# Nikola98p_M_2-ESP32-S3_N16R8-Dev-Board__.net
KiCad netlist of a schematic drawn in Altium Designer
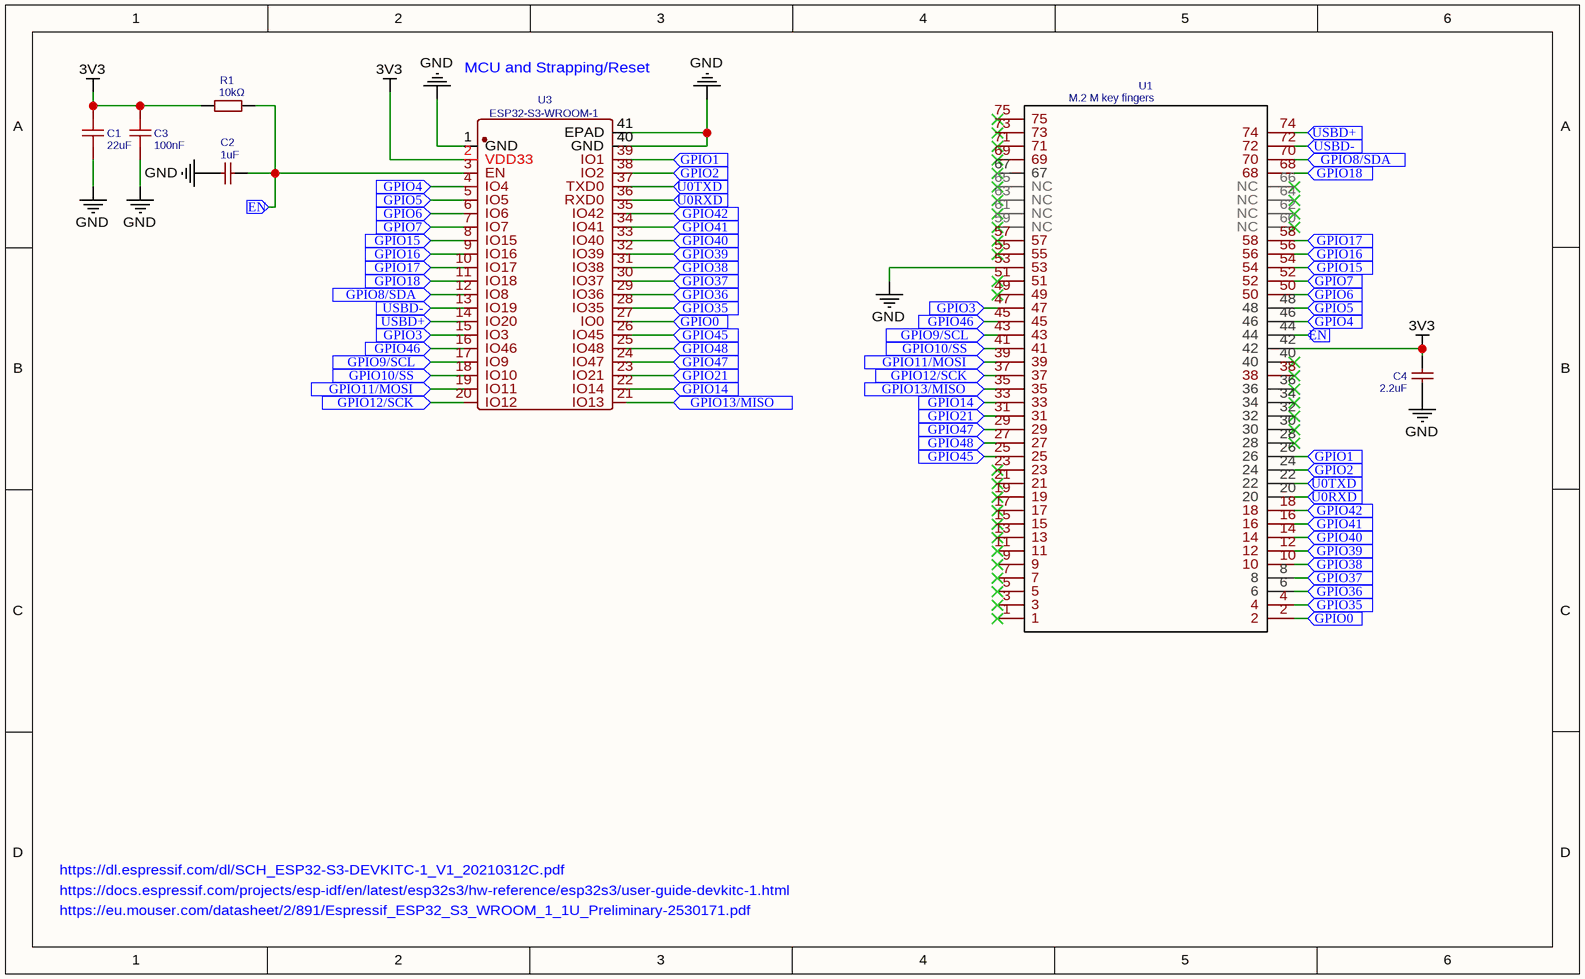
[diagram p0: Nikola98p_M.2-ESP32-S3_N16R8-Dev-Board__Altium__ESP32-S3-M.2_2024-03-15.schdoc]

(export (version "E")
  (design (tool "Eeschema 10.0.6"))
  (components
    (comp (ref "C1")
      (value "22uF")
      (fields
        (field (name "MANUFACTURER") "SAMSUNG(三星)")
        (field (name "MANUFACTURER PART") "CL10A226MQ8NRNC")
      )
      (libsource (lib "altium-import") (part "root_1_22uF_"))
    )
    (comp (ref "C2")
      (value "1uF")
      (fields
        (field (name "MANUFACTURER PART") "CL10A105KB8NNNC")
        (field (name "MANUFACTURER") "SAMSUNG(三星)")
      )
      (libsource (lib "altium-import") (part "root_0_1uF_"))
    )
    (comp (ref "C3")
      (value "100nF")
      (fields
        (field (name "MANUFACTURER") "YAGEO(国巨)")
        (field (name "MANUFACTURER PART") "CC0603KRX7R9BB104")
      )
      (libsource (lib "altium-import") (part "root_1_100nF_"))
    )
    (comp (ref "C4")
      (value "2.2uF")
      (fields
        (field (name "MANUFACTURER PART") "CL10A225KP8NNNC")
        (field (name "MANUFACTURER") "SAMSUNG(三星)")
      )
      (libsource (lib "altium-import") (part "root_1_2.2uF_"))
    )
    (comp (ref "R1")
      (value "10kΩ")
      (fields (field (name "MANUFACTURER") "YAGEO(国巨)") (field (name "MANUFACTURER PART") "RC0603FR-0710KL"))
      (libsource (lib "altium-import") (part "root_0_10kΩ_"))
    )
    (comp (ref "U1")
      (value "M.2 M key fingers")
      (fields (field (name "CONTRIBUTOR") "Nikola Pantelin"))
      (libsource (lib "altium-import") (part "root_0_M.2 M key fingers_"))
    )
    (comp (ref "U3")
      (value "ESP32-S3-WROOM-1")
      (fields (field (name "MANUFACTURER") "Espressif Systems") (field (name "CONTRIBUTOR") "max30012540"))
      (libsource (lib "altium-import") (part "root_0_ESP32-S3-WROOM-1_"))
    )
  )
  (nets
    (net (code "1") (name "/EN") (class "Default")
      (node (ref "C2") (pin "2") (pinfunction "2_2") (pintype "passive"))
      (node (ref "R1") (pin "2") (pinfunction "2_2") (pintype "passive"))
      (node (ref "U1") (pin "44") (pinfunction "44_44") (pintype "passive"))
      (node (ref "U3") (pin "3") (pinfunction "EN_3") (pintype "passive"))
    )
    (net (code "2") (name "/GPIO0") (class "Default")
      (node (ref "U1") (pin "2") (pinfunction "2_2") (pintype "passive"))
      (node (ref "U3") (pin "27") (pinfunction "IO0_27") (pintype "passive"))
    )
    (net (code "3") (name "/GPIO1") (class "Default")
      (node (ref "U1") (pin "26") (pinfunction "26_26") (pintype "passive"))
      (node (ref "U3") (pin "39") (pinfunction "IO1_39") (pintype "passive"))
    )
    (net (code "4") (name "/GPIO2") (class "Default")
      (node (ref "U1") (pin "24") (pinfunction "24_24") (pintype "passive"))
      (node (ref "U3") (pin "38") (pinfunction "IO2_38") (pintype "passive"))
    )
    (net (code "5") (name "/GPIO3") (class "Default")
      (node (ref "U1") (pin "47") (pinfunction "47_47") (pintype "passive"))
      (node (ref "U3") (pin "15") (pinfunction "IO3_15") (pintype "passive"))
    )
    (net (code "6") (name "/GPIO4") (class "Default")
      (node (ref "U1") (pin "46") (pinfunction "46_46") (pintype "passive"))
      (node (ref "U3") (pin "4") (pinfunction "IO4_4") (pintype "passive"))
    )
    (net (code "7") (name "/GPIO5") (class "Default")
      (node (ref "U1") (pin "48") (pinfunction "48_48") (pintype "passive"))
      (node (ref "U3") (pin "5") (pinfunction "IO5_5") (pintype "passive"))
    )
    (net (code "8") (name "/GPIO6") (class "Default")
      (node (ref "U1") (pin "50") (pinfunction "50_50") (pintype "passive"))
      (node (ref "U3") (pin "6") (pinfunction "IO6_6") (pintype "passive"))
    )
    (net (code "9") (name "/GPIO7") (class "Default")
      (node (ref "U1") (pin "52") (pinfunction "52_52") (pintype "passive"))
      (node (ref "U3") (pin "7") (pinfunction "IO7_7") (pintype "passive"))
    )
    (net (code "10") (name "/GPIO8{slash}SDA") (class "Default")
      (node (ref "U1") (pin "70") (pinfunction "70_70") (pintype "passive"))
      (node (ref "U3") (pin "12") (pinfunction "IO8_12") (pintype "passive"))
    )
    (net (code "11") (name "/GPIO9{slash}SCL") (class "Default")
      (node (ref "U1") (pin "43") (pinfunction "43_43") (pintype "passive"))
      (node (ref "U3") (pin "17") (pinfunction "IO9_17") (pintype "passive"))
    )
    (net (code "12") (name "/GPIO10{slash}SS") (class "Default")
      (node (ref "U1") (pin "41") (pinfunction "41_41") (pintype "passive"))
      (node (ref "U3") (pin "18") (pinfunction "IO10_18") (pintype "passive"))
    )
    (net (code "13") (name "/GPIO11{slash}MOSI") (class "Default")
      (node (ref "U1") (pin "39") (pinfunction "39_39") (pintype "passive"))
      (node (ref "U3") (pin "19") (pinfunction "IO11_19") (pintype "passive"))
    )
    (net (code "14") (name "/GPIO12{slash}SCK") (class "Default")
      (node (ref "U1") (pin "37") (pinfunction "37_37") (pintype "passive"))
      (node (ref "U3") (pin "20") (pinfunction "IO12_20") (pintype "passive"))
    )
    (net (code "15") (name "/GPIO13{slash}MISO") (class "Default")
      (node (ref "U1") (pin "35") (pinfunction "35_35") (pintype "passive"))
      (node (ref "U3") (pin "21") (pinfunction "IO13_21") (pintype "passive"))
    )
    (net (code "16") (name "/GPIO14") (class "Default")
      (node (ref "U1") (pin "33") (pinfunction "33_33") (pintype "passive"))
      (node (ref "U3") (pin "22") (pinfunction "IO14_22") (pintype "passive"))
    )
    (net (code "17") (name "/GPIO15") (class "Default")
      (node (ref "U1") (pin "54") (pinfunction "54_54") (pintype "passive"))
      (node (ref "U3") (pin "8") (pinfunction "IO15_8") (pintype "passive"))
    )
    (net (code "18") (name "/GPIO16") (class "Default")
      (node (ref "U1") (pin "56") (pinfunction "56_56") (pintype "passive"))
      (node (ref "U3") (pin "9") (pinfunction "IO16_9") (pintype "passive"))
    )
    (net (code "19") (name "/GPIO17") (class "Default")
      (node (ref "U1") (pin "58") (pinfunction "58_58") (pintype "passive"))
      (node (ref "U3") (pin "10") (pinfunction "IO17_10") (pintype "passive"))
    )
    (net (code "20") (name "/GPIO18") (class "Default")
      (node (ref "U1") (pin "68") (pinfunction "68_68") (pintype "passive"))
      (node (ref "U3") (pin "11") (pinfunction "IO18_11") (pintype "passive"))
    )
    (net (code "21") (name "/GPIO21") (class "Default")
      (node (ref "U1") (pin "31") (pinfunction "31_31") (pintype "passive"))
      (node (ref "U3") (pin "23") (pinfunction "IO21_23") (pintype "passive"))
    )
    (net (code "22") (name "/GPIO35") (class "Default")
      (node (ref "U1") (pin "4") (pinfunction "4_4") (pintype "passive"))
      (node (ref "U3") (pin "28") (pinfunction "IO35_28") (pintype "passive"))
    )
    (net (code "23") (name "/GPIO36") (class "Default")
      (node (ref "U1") (pin "6") (pinfunction "6_6") (pintype "passive"))
      (node (ref "U3") (pin "29") (pinfunction "IO36_29") (pintype "passive"))
    )
    (net (code "24") (name "/GPIO37") (class "Default")
      (node (ref "U1") (pin "8") (pinfunction "8_8") (pintype "passive"))
      (node (ref "U3") (pin "30") (pinfunction "IO37_30") (pintype "passive"))
    )
    (net (code "25") (name "/GPIO38") (class "Default")
      (node (ref "U1") (pin "10") (pinfunction "10_10") (pintype "passive"))
      (node (ref "U3") (pin "31") (pinfunction "IO38_31") (pintype "passive"))
    )
    (net (code "26") (name "/GPIO39") (class "Default")
      (node (ref "U1") (pin "12") (pinfunction "12_12") (pintype "passive"))
      (node (ref "U3") (pin "32") (pinfunction "IO39_32") (pintype "passive"))
    )
    (net (code "27") (name "/GPIO40") (class "Default")
      (node (ref "U1") (pin "14") (pinfunction "14_14") (pintype "passive"))
      (node (ref "U3") (pin "33") (pinfunction "IO40_33") (pintype "passive"))
    )
    (net (code "28") (name "/GPIO41") (class "Default")
      (node (ref "U1") (pin "16") (pinfunction "16_16") (pintype "passive"))
      (node (ref "U3") (pin "34") (pinfunction "IO41_34") (pintype "passive"))
    )
    (net (code "29") (name "/GPIO42") (class "Default")
      (node (ref "U1") (pin "18") (pinfunction "18_18") (pintype "passive"))
      (node (ref "U3") (pin "35") (pinfunction "IO42_35") (pintype "passive"))
    )
    (net (code "30") (name "/GPIO45") (class "Default")
      (node (ref "U1") (pin "25") (pinfunction "25_25") (pintype "passive"))
      (node (ref "U3") (pin "26") (pinfunction "IO45_26") (pintype "passive"))
    )
    (net (code "31") (name "/GPIO46") (class "Default")
      (node (ref "U1") (pin "45") (pinfunction "45_45") (pintype "passive"))
      (node (ref "U3") (pin "16") (pinfunction "IO46_16") (pintype "passive"))
    )
    (net (code "32") (name "/GPIO47") (class "Default")
      (node (ref "U1") (pin "29") (pinfunction "29_29") (pintype "passive"))
      (node (ref "U3") (pin "24") (pinfunction "IO47_24") (pintype "passive"))
    )
    (net (code "33") (name "/GPIO48") (class "Default")
      (node (ref "U1") (pin "27") (pinfunction "27_27") (pintype "passive"))
      (node (ref "U3") (pin "25") (pinfunction "IO48_25") (pintype "passive"))
    )
    (net (code "34") (name "/U0RXD") (class "Default")
      (node (ref "U1") (pin "20") (pinfunction "20_20") (pintype "passive"))
      (node (ref "U3") (pin "36") (pinfunction "RXD0_36") (pintype "passive"))
    )
    (net (code "35") (name "/U0TXD") (class "Default")
      (node (ref "U1") (pin "22") (pinfunction "22_22") (pintype "passive"))
      (node (ref "U3") (pin "37") (pinfunction "TXD0_37") (pintype "passive"))
    )
    (net (code "36") (name "/USBD+") (class "Default")
      (node (ref "U1") (pin "74") (pinfunction "74_74") (pintype "passive"))
      (node (ref "U3") (pin "14") (pinfunction "IO20_14") (pintype "passive"))
    )
    (net (code "37") (name "/USBD-") (class "Default")
      (node (ref "U1") (pin "72") (pinfunction "72_72") (pintype "passive"))
      (node (ref "U3") (pin "13") (pinfunction "IO19_13") (pintype "passive"))
    )
    (net (code "38") (name "3V3") (class "Default")
      (node (ref "C1") (pin "2") (pinfunction "2_2") (pintype "passive"))
      (node (ref "C3") (pin "2") (pinfunction "2_2") (pintype "passive"))
      (node (ref "C4") (pin "2") (pinfunction "2_2") (pintype "passive"))
      (node (ref "R1") (pin "1") (pinfunction "1_1") (pintype "passive"))
      (node (ref "U1") (pin "42") (pinfunction "42_42") (pintype "passive"))
      (node (ref "U3") (pin "2") (pinfunction "VDD33_2") (pintype "passive"))
    )
    (net (code "39") (name "GND") (class "Default")
      (node (ref "C1") (pin "1") (pinfunction "1_1") (pintype "passive"))
      (node (ref "C2") (pin "1") (pinfunction "1_1") (pintype "passive"))
      (node (ref "C3") (pin "1") (pinfunction "1_1") (pintype "passive"))
      (node (ref "C4") (pin "1") (pinfunction "1_1") (pintype "passive"))
      (node (ref "U1") (pin "53") (pinfunction "53_53") (pintype "passive"))
      (node (ref "U3") (pin "1") (pinfunction "GND_1") (pintype "passive"))
      (node (ref "U3") (pin "40") (pinfunction "GND_40") (pintype "passive"))
      (node (ref "U3") (pin "41") (pinfunction "EPAD_41") (pintype "passive"))
    )
    (net (code "40") (name "unconnected-(U1-NC-Pad59)") (class "Default")
      (node (ref "U1") (pin "59") (pinfunction "NC_59") (pintype "passive+no_connect"))
    )
    (net (code "41") (name "unconnected-(U1-NC-Pad60)") (class "Default")
      (node (ref "U1") (pin "60") (pinfunction "NC_60") (pintype "passive+no_connect"))
    )
    (net (code "42") (name "unconnected-(U1-NC-Pad61)") (class "Default")
      (node (ref "U1") (pin "61") (pinfunction "NC_61") (pintype "passive+no_connect"))
    )
    (net (code "43") (name "unconnected-(U1-NC-Pad62)") (class "Default")
      (node (ref "U1") (pin "62") (pinfunction "NC_62") (pintype "passive+no_connect"))
    )
    (net (code "44") (name "unconnected-(U1-NC-Pad63)") (class "Default")
      (node (ref "U1") (pin "63") (pinfunction "NC_63") (pintype "passive+no_connect"))
    )
    (net (code "45") (name "unconnected-(U1-NC-Pad64)") (class "Default")
      (node (ref "U1") (pin "64") (pinfunction "NC_64") (pintype "passive+no_connect"))
    )
    (net (code "46") (name "unconnected-(U1-NC-Pad65)") (class "Default")
      (node (ref "U1") (pin "65") (pinfunction "NC_65") (pintype "passive+no_connect"))
    )
    (net (code "47") (name "unconnected-(U1-NC-Pad66)") (class "Default")
      (node (ref "U1") (pin "66") (pinfunction "NC_66") (pintype "passive+no_connect"))
    )
    (net (code "48") (name "unconnected-(U1-Pad1)") (class "Default")
      (node (ref "U1") (pin "1") (pinfunction "1_1") (pintype "passive+no_connect"))
    )
    (net (code "49") (name "unconnected-(U1-Pad3)") (class "Default")
      (node (ref "U1") (pin "3") (pinfunction "3_3") (pintype "passive+no_connect"))
    )
    (net (code "50") (name "unconnected-(U1-Pad5)") (class "Default")
      (node (ref "U1") (pin "5") (pinfunction "5_5") (pintype "passive+no_connect"))
    )
    (net (code "51") (name "unconnected-(U1-Pad7)") (class "Default")
      (node (ref "U1") (pin "7") (pinfunction "7_7") (pintype "passive+no_connect"))
    )
    (net (code "52") (name "unconnected-(U1-Pad9)") (class "Default")
      (node (ref "U1") (pin "9") (pinfunction "9_9") (pintype "passive+no_connect"))
    )
    (net (code "53") (name "unconnected-(U1-Pad11)") (class "Default")
      (node (ref "U1") (pin "11") (pinfunction "11_11") (pintype "passive+no_connect"))
    )
    (net (code "54") (name "unconnected-(U1-Pad13)") (class "Default")
      (node (ref "U1") (pin "13") (pinfunction "13_13") (pintype "passive+no_connect"))
    )
    (net (code "55") (name "unconnected-(U1-Pad15)") (class "Default")
      (node (ref "U1") (pin "15") (pinfunction "15_15") (pintype "passive+no_connect"))
    )
    (net (code "56") (name "unconnected-(U1-Pad17)") (class "Default")
      (node (ref "U1") (pin "17") (pinfunction "17_17") (pintype "passive+no_connect"))
    )
    (net (code "57") (name "unconnected-(U1-Pad19)") (class "Default")
      (node (ref "U1") (pin "19") (pinfunction "19_19") (pintype "passive+no_connect"))
    )
    (net (code "58") (name "unconnected-(U1-Pad21)") (class "Default")
      (node (ref "U1") (pin "21") (pinfunction "21_21") (pintype "passive+no_connect"))
    )
    (net (code "59") (name "unconnected-(U1-Pad23)") (class "Default")
      (node (ref "U1") (pin "23") (pinfunction "23_23") (pintype "passive+no_connect"))
    )
    (net (code "60") (name "unconnected-(U1-Pad28)") (class "Default")
      (node (ref "U1") (pin "28") (pinfunction "28_28") (pintype "passive+no_connect"))
    )
    (net (code "61") (name "unconnected-(U1-Pad30)") (class "Default")
      (node (ref "U1") (pin "30") (pinfunction "30_30") (pintype "passive+no_connect"))
    )
    (net (code "62") (name "unconnected-(U1-Pad32)") (class "Default")
      (node (ref "U1") (pin "32") (pinfunction "32_32") (pintype "passive+no_connect"))
    )
    (net (code "63") (name "unconnected-(U1-Pad34)") (class "Default")
      (node (ref "U1") (pin "34") (pinfunction "34_34") (pintype "passive+no_connect"))
    )
    (net (code "64") (name "unconnected-(U1-Pad36)") (class "Default")
      (node (ref "U1") (pin "36") (pinfunction "36_36") (pintype "passive+no_connect"))
    )
    (net (code "65") (name "unconnected-(U1-Pad38)") (class "Default")
      (node (ref "U1") (pin "38") (pinfunction "38_38") (pintype "passive+no_connect"))
    )
    (net (code "66") (name "unconnected-(U1-Pad40)") (class "Default")
      (node (ref "U1") (pin "40") (pinfunction "40_40") (pintype "passive+no_connect"))
    )
    (net (code "67") (name "unconnected-(U1-Pad49)") (class "Default")
      (node (ref "U1") (pin "49") (pinfunction "49_49") (pintype "passive+no_connect"))
    )
    (net (code "68") (name "unconnected-(U1-Pad51)") (class "Default")
      (node (ref "U1") (pin "51") (pinfunction "51_51") (pintype "passive+no_connect"))
    )
    (net (code "69") (name "unconnected-(U1-Pad55)") (class "Default")
      (node (ref "U1") (pin "55") (pinfunction "55_55") (pintype "passive+no_connect"))
    )
    (net (code "70") (name "unconnected-(U1-Pad57)") (class "Default")
      (node (ref "U1") (pin "57") (pinfunction "57_57") (pintype "passive+no_connect"))
    )
    (net (code "71") (name "unconnected-(U1-Pad67)") (class "Default")
      (node (ref "U1") (pin "67") (pinfunction "67_67") (pintype "passive+no_connect"))
    )
    (net (code "72") (name "unconnected-(U1-Pad69)") (class "Default")
      (node (ref "U1") (pin "69") (pinfunction "69_69") (pintype "passive+no_connect"))
    )
    (net (code "73") (name "unconnected-(U1-Pad71)") (class "Default")
      (node (ref "U1") (pin "71") (pinfunction "71_71") (pintype "passive+no_connect"))
    )
    (net (code "74") (name "unconnected-(U1-Pad73)") (class "Default")
      (node (ref "U1") (pin "73") (pinfunction "73_73") (pintype "passive+no_connect"))
    )
    (net (code "75") (name "unconnected-(U1-Pad75)") (class "Default")
      (node (ref "U1") (pin "75") (pinfunction "75_75") (pintype "passive+no_connect"))
    )
  )
)
